# LcsNodes-Building-Block-USB-Serial-IO.net
KiCad netlist of a schematic drawn in EasyEDA
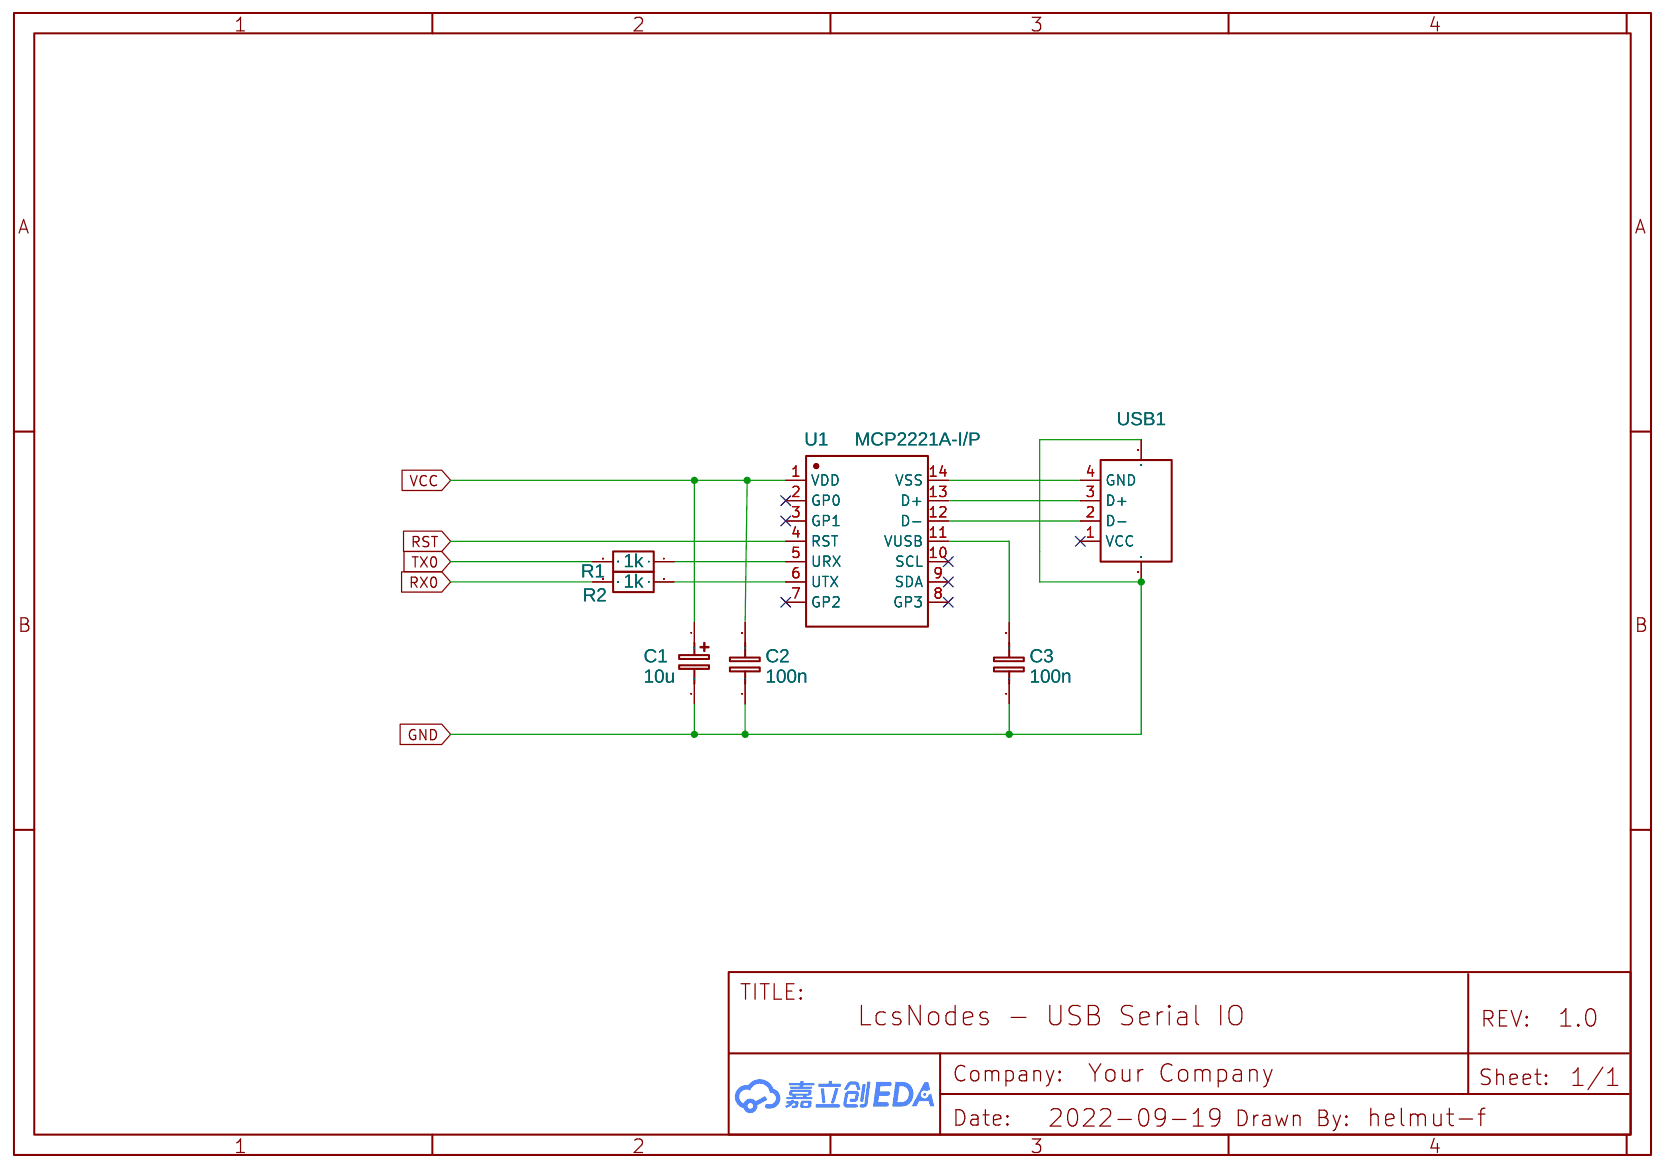
[diagram p0: schematic sheet]

(export (version "E")
  (design (tool "Eeschema 10.0.6"))
  (components
    (comp (ref "C1") (value "10u") (libsource (lib "") (part "CE_TH_D4.0×F1.5_EU")))
    (comp (ref "C2") (value "100n") (libsource (lib "") (part "C_0603_EU")))
    (comp (ref "C3") (value "100n") (libsource (lib "") (part "C_0603_EU")))
    (comp (ref "R1") (value "1k") (libsource (lib "") (part "R_AXIAL-0.3_EU")))
    (comp (ref "R2") (value "1k") (libsource (lib "") (part "R_AXIAL-0.3_EU")))
    (comp (ref "U1") (value "MCP2221A-I/P") (libsource (lib "") (part "MCP2221A-I/P")))
    (comp (ref "USB1")
      (value "USB-Type A_Male")
      (fields (field (name "BOM_Manufacturer Part") "USB-05") (field (name "BOM_Supplier Part") "C112454"))
      (libsource (lib "") (part "USB-Type A_Male"))
    )
  )
  (nets
    (net (code "1") (name "GND") (class "Default")
      (node (ref "C1") (pin "2") (pinfunction "2_2") (pintype "unspecified"))
      (node (ref "C2") (pin "1") (pinfunction "1_1") (pintype "unspecified"))
      (node (ref "C3") (pin "1") (pinfunction "1_1") (pintype "unspecified"))
      (node (ref "USB1") (pin "5") (pinfunction "5_5") (pintype "unspecified"))
      (node (ref "USB1") (pin "6") (pinfunction "6_6") (pintype "unspecified"))
    )
    (net (code "2") (name "Net-(U1-D+)") (class "Default")
      (node (ref "U1") (pin "13") (pinfunction "D+_13") (pintype "unspecified"))
      (node (ref "USB1") (pin "3") (pinfunction "D+_3") (pintype "input"))
    )
    (net (code "3") (name "Net-(U1-D-)") (class "Default")
      (node (ref "U1") (pin "12") (pinfunction "D-_12") (pintype "unspecified"))
      (node (ref "USB1") (pin "2") (pinfunction "D-_2") (pintype "input"))
    )
    (net (code "4") (name "Net-(U1-URX)") (class "Default")
      (node (ref "R1") (pin "1") (pinfunction "1_1") (pintype "unspecified"))
      (node (ref "U1") (pin "5") (pinfunction "URX_5") (pintype "unspecified"))
    )
    (net (code "5") (name "Net-(U1-UTX)") (class "Default")
      (node (ref "R2") (pin "1") (pinfunction "1_1") (pintype "unspecified"))
      (node (ref "U1") (pin "6") (pinfunction "UTX_6") (pintype "unspecified"))
    )
    (net (code "6") (name "Net-(U1-VSS)") (class "Default")
      (node (ref "U1") (pin "14") (pinfunction "VSS_14") (pintype "unspecified"))
      (node (ref "USB1") (pin "4") (pinfunction "GND_4") (pintype "input"))
    )
    (net (code "7") (name "Net-(U1-VUSB)") (class "Default")
      (node (ref "C3") (pin "2") (pinfunction "2_2") (pintype "unspecified"))
      (node (ref "U1") (pin "11") (pinfunction "VUSB_11") (pintype "unspecified"))
    )
    (net (code "8") (name "RST") (class "Default")
      (node (ref "U1") (pin "4") (pinfunction "RST_4") (pintype "unspecified"))
    )
    (net (code "9") (name "RX0") (class "Default")
      (node (ref "R2") (pin "2") (pinfunction "2_2") (pintype "unspecified"))
    )
    (net (code "10") (name "TX0") (class "Default")
      (node (ref "R1") (pin "2") (pinfunction "2_2") (pintype "unspecified"))
    )
    (net (code "11") (name "VCC") (class "Default")
      (node (ref "C1") (pin "1") (pinfunction "1_1") (pintype "unspecified"))
      (node (ref "C2") (pin "2") (pinfunction "2_2") (pintype "unspecified"))
      (node (ref "U1") (pin "1") (pinfunction "VDD_1") (pintype "unspecified"))
    )
    (net (code "12") (name "unconnected-(U1-GP0-Pad2)") (class "Default")
      (node (ref "U1") (pin "2") (pinfunction "GP0_2") (pintype "unspecified+no_connect"))
    )
    (net (code "13") (name "unconnected-(U1-GP1-Pad3)") (class "Default")
      (node (ref "U1") (pin "3") (pinfunction "GP1_3") (pintype "unspecified+no_connect"))
    )
    (net (code "14") (name "unconnected-(U1-GP2-Pad7)") (class "Default")
      (node (ref "U1") (pin "7") (pinfunction "GP2_7") (pintype "unspecified+no_connect"))
    )
    (net (code "15") (name "unconnected-(U1-GP3-Pad8)") (class "Default")
      (node (ref "U1") (pin "8") (pinfunction "GP3_8") (pintype "unspecified+no_connect"))
    )
    (net (code "16") (name "unconnected-(U1-SCL-Pad10)") (class "Default")
      (node (ref "U1") (pin "10") (pinfunction "SCL_10") (pintype "unspecified+no_connect"))
    )
    (net (code "17") (name "unconnected-(U1-SDA-Pad9)") (class "Default")
      (node (ref "U1") (pin "9") (pinfunction "SDA_9") (pintype "unspecified+no_connect"))
    )
    (net (code "18") (name "unconnected-(USB1-VCC-Pad1)") (class "Default")
      (node (ref "USB1") (pin "1") (pinfunction "VCC_1") (pintype "input+no_connect"))
    )
  )
)
